# HPS_IOs.net
KiCad netlist of a schematic drawn in Altium Designer
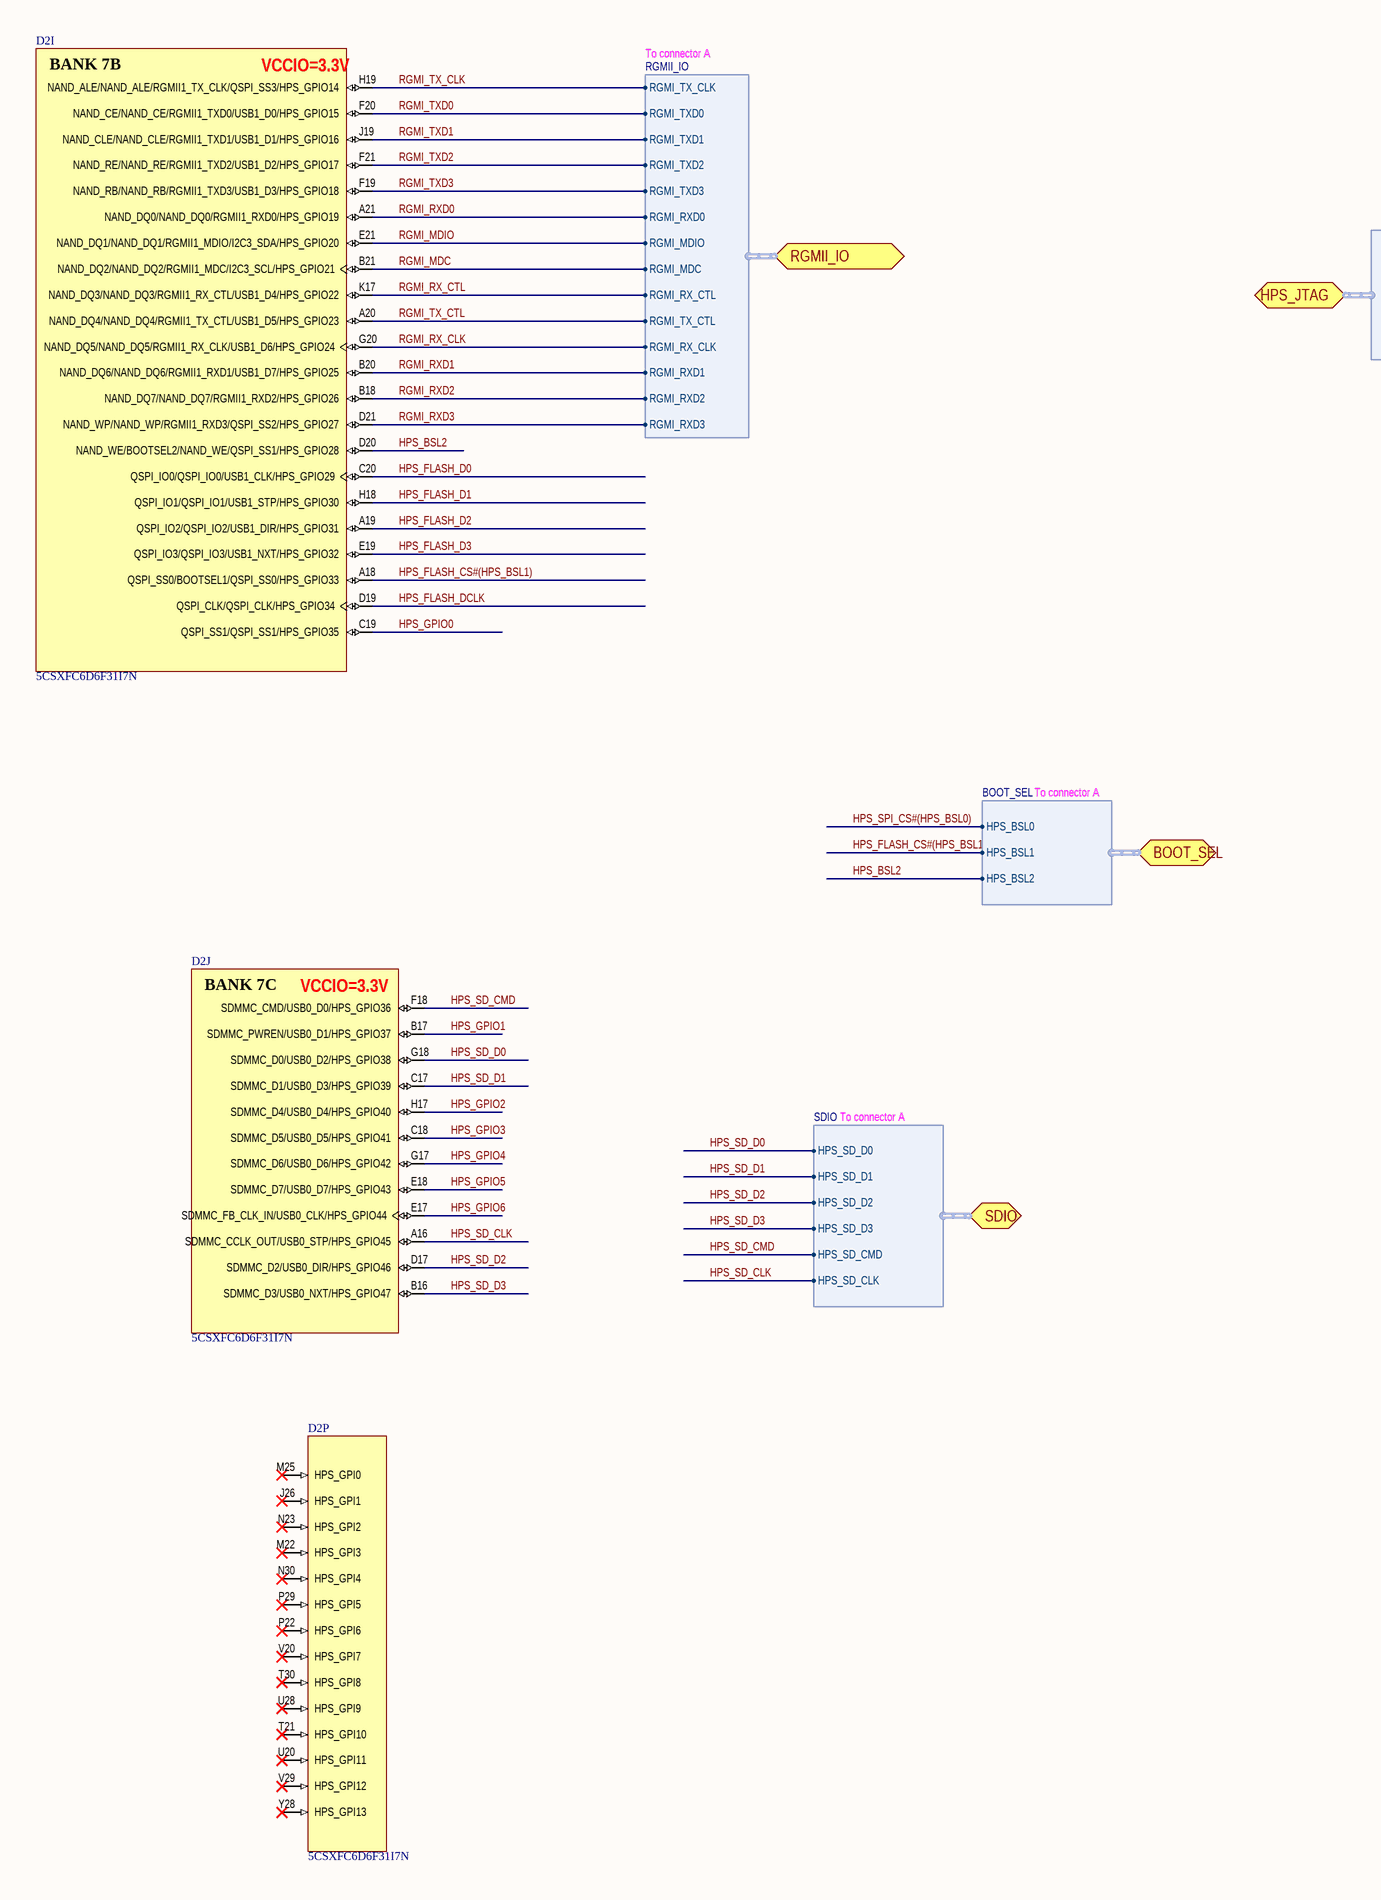
[diagram p0: HPS_IOs.SchDoc, left]
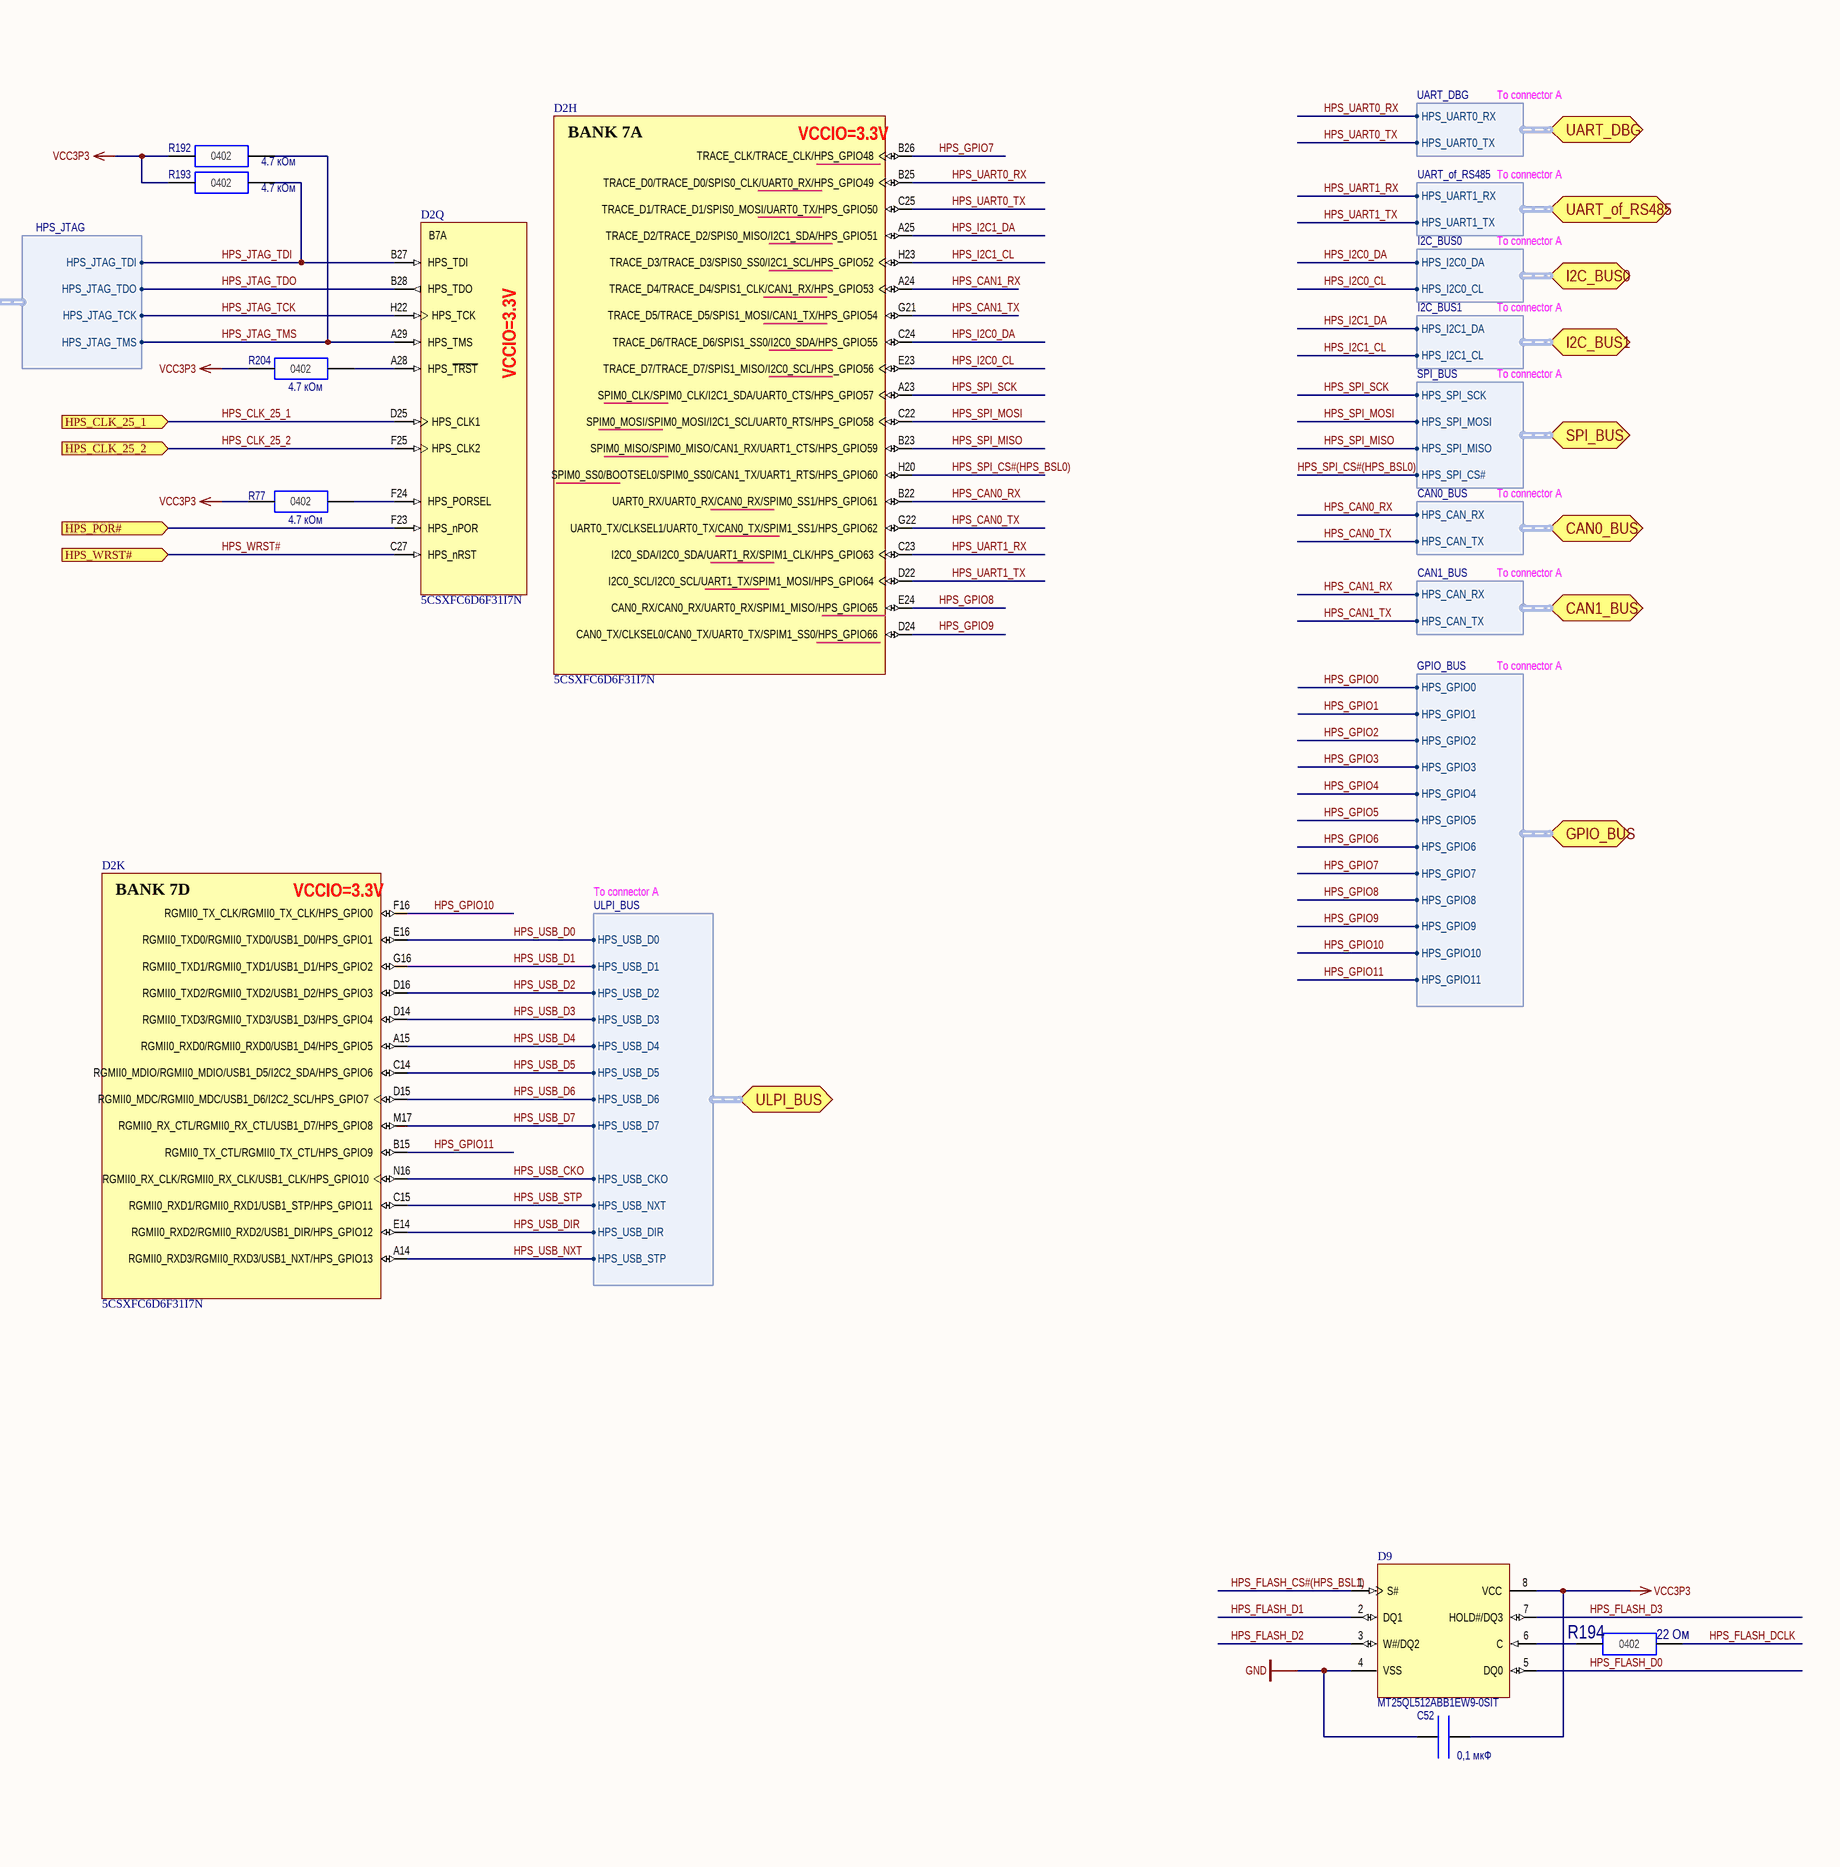
[diagram p1: HPS_IOs.SchDoc, right]

(export (version "E")
  (design (tool "Eeschema 10.0.6"))
  (components
    (comp (ref "C52")
      (value "0,1 мкФ")
      (footprint "CC0402(1005)")
      (description "Чип конденсатор керамический")
      (fields (field (name "Comment") "CC0402-X7R-0,1 мкФ-20%-10В"))
      (libsource (lib "Чип конденсаторы") (part "CC0402-X7R-#-20%-10В"))
    )
    (comp (ref "D2")
      (value "5CSXFC6D6F31I7N")
      (footprint "ALTR-FBGA896_A-200")
      (fields (field (name "MANUFACTURER") "Altera"))
      (libsource (lib "") (part "5CSXFC6D6F31I7N_1"))
    )
    (comp (ref "D9")
      (value "MT25QL512ABB1EW9-0SIT")
      (footprint "SON127P800X80_HS-9N")
      (fields (field (name "VOLTAGE") "2.7V-3.6V ") (field (name "MANUFACTURER") "Micron"))
      (libsource (lib "SD_IC") (part "MT25QL512ABB1EW9-0SIT"))
    )
    (comp (ref "R77")
      (value "4.7 кОм")
      (footprint "CR0402(1005)")
      (description "Чип резистор")
      (fields (field (name "TOLERANCE") "5%") (field (name "Comment") "CR0402-4.7 кОм-±5%"))
      (libsource (lib "Резисторы") (part "CR0402-#-±5%"))
    )
    (comp (ref "R192")
      (value "4.7 кОм")
      (footprint "CR0402(1005)")
      (description "Чип резистор")
      (fields (field (name "TOLERANCE") "5%") (field (name "Comment") "CR0402-4.7 кОм-±5%"))
      (libsource (lib "Резисторы") (part "CR0402-#-±5%"))
    )
    (comp (ref "R193")
      (value "4.7 кОм")
      (footprint "CR0402(1005)")
      (description "Чип резистор")
      (fields (field (name "TOLERANCE") "5%") (field (name "Comment") "CR0402-4.7 кОм-±5%"))
      (libsource (lib "Резисторы") (part "CR0402-#-±5%"))
    )
    (comp (ref "R194")
      (value "22 Ом")
      (footprint "CR0402(1005)")
      (description "Чип резистор")
      (fields (field (name "TOLERANCE") "5%") (field (name "Comment") "CR0402-22 Ом-±5%"))
      (libsource (lib "Чип резисторы") (part "CR0402-#-±5%"))
    )
    (comp (ref "R204")
      (value "4.7 кОм")
      (footprint "CR0402(1005)")
      (description "Чип резистор")
      (fields (field (name "TOLERANCE") "5%") (field (name "Comment") "CR0402-4.7 кОм-±5%"))
      (libsource (lib "Резисторы") (part "CR0402-#-±5%"))
    )
  )
  (nets
    (net (code "14") (name "/HPS_BSL2") (class "Default")
      (node (ref "D2") (pin "D20") (pinfunction "NAND_WE/BOOTSEL2/NAND_WE/QSPI_SS1/HPS_GPIO28_D20") (pintype "bidirectional"))
    )
    (net (code "15") (name "/HPS_CAN0_RX") (class "Default")
      (node (ref "D2") (pin "B22") (pinfunction "UART0_RX/UART0_RX/CAN0_RX/SPIM0_SS1/HPS_GPIO61_B22") (pintype "bidirectional"))
    )
    (net (code "16") (name "/HPS_CAN0_TX") (class "Default")
      (node (ref "D2") (pin "G22") (pinfunction "UART0_TX/CLKSEL1/UART0_TX/CAN0_TX/SPIM1_SS1/HPS_GPIO62_G22") (pintype "bidirectional"))
    )
    (net (code "17") (name "/HPS_CAN1_RX") (class "Default")
      (node (ref "D2") (pin "A24") (pinfunction "TRACE_D4/TRACE_D4/SPIS1_CLK/CAN1_RX/HPS_GPIO53_A24") (pintype "bidirectional"))
    )
    (net (code "18") (name "/HPS_CAN1_TX") (class "Default")
      (node (ref "D2") (pin "G21") (pinfunction "TRACE_D5/TRACE_D5/SPIS1_MOSI/CAN1_TX/HPS_GPIO54_G21") (pintype "bidirectional"))
    )
    (net (code "19") (name "/HPS_CLK_25_1") (class "Default")
      (node (ref "D2") (pin "D25") (pinfunction "HPS_CLK1_D25") (pintype "input"))
    )
    (net (code "20") (name "/HPS_CLK_25_2") (class "Default")
      (node (ref "D2") (pin "F25") (pinfunction "HPS_CLK2_F25") (pintype "input"))
    )
    (net (code "21") (name "/HPS_FLASH_CS#(HPS_BSL1)") (class "Default")
      (node (ref "D2") (pin "A18") (pinfunction "QSPI_SS0/BOOTSEL1/QSPI_SS0/HPS_GPIO33_A18") (pintype "bidirectional"))
      (node (ref "D9") (pin "1") (pinfunction "S#_1") (pintype "input"))
    )
    (net (code "22") (name "/HPS_FLASH_D0") (class "Default")
      (node (ref "D2") (pin "C20") (pinfunction "QSPI_IO0/QSPI_IO0/USB1_CLK/HPS_GPIO29_C20") (pintype "bidirectional"))
      (node (ref "D9") (pin "5") (pinfunction "DQ0_5") (pintype "bidirectional"))
    )
    (net (code "23") (name "/HPS_FLASH_D1") (class "Default")
      (node (ref "D2") (pin "H18") (pinfunction "QSPI_IO1/QSPI_IO1/USB1_STP/HPS_GPIO30_H18") (pintype "bidirectional"))
      (node (ref "D9") (pin "2") (pinfunction "DQ1_2") (pintype "bidirectional"))
    )
    (net (code "24") (name "/HPS_FLASH_D2") (class "Default")
      (node (ref "D2") (pin "A19") (pinfunction "QSPI_IO2/QSPI_IO2/USB1_DIR/HPS_GPIO31_A19") (pintype "bidirectional"))
      (node (ref "D9") (pin "3") (pinfunction "W#/DQ2_3") (pintype "bidirectional"))
    )
    (net (code "25") (name "/HPS_FLASH_D3") (class "Default")
      (node (ref "D2") (pin "E19") (pinfunction "QSPI_IO3/QSPI_IO3/USB1_NXT/HPS_GPIO32_E19") (pintype "bidirectional"))
      (node (ref "D9") (pin "7") (pinfunction "HOLD#/DQ3_7") (pintype "bidirectional"))
    )
    (net (code "26") (name "/HPS_FLASH_DCLK") (class "Default")
      (node (ref "D2") (pin "D19") (pinfunction "QSPI_CLK/QSPI_CLK/HPS_GPIO34_D19") (pintype "bidirectional"))
      (node (ref "R194") (pin "2") (pinfunction "-_2") (pintype "passive"))
    )
    (net (code "27") (name "/HPS_GPIO0") (class "Default")
      (node (ref "D2") (pin "C19") (pinfunction "QSPI_SS1/QSPI_SS1/HPS_GPIO35_C19") (pintype "bidirectional"))
    )
    (net (code "28") (name "/HPS_GPIO1") (class "Default")
      (node (ref "D2") (pin "B17") (pinfunction "SDMMC_PWREN/USB0_D1/HPS_GPIO37_B17") (pintype "bidirectional"))
    )
    (net (code "29") (name "/HPS_GPIO2") (class "Default")
      (node (ref "D2") (pin "H17") (pinfunction "SDMMC_D4/USB0_D4/HPS_GPIO40_H17") (pintype "bidirectional"))
    )
    (net (code "30") (name "/HPS_GPIO3") (class "Default")
      (node (ref "D2") (pin "C18") (pinfunction "SDMMC_D5/USB0_D5/HPS_GPIO41_C18") (pintype "bidirectional"))
    )
    (net (code "31") (name "/HPS_GPIO4") (class "Default")
      (node (ref "D2") (pin "G17") (pinfunction "SDMMC_D6/USB0_D6/HPS_GPIO42_G17") (pintype "bidirectional"))
    )
    (net (code "32") (name "/HPS_GPIO5") (class "Default")
      (node (ref "D2") (pin "E18") (pinfunction "SDMMC_D7/USB0_D7/HPS_GPIO43_E18") (pintype "bidirectional"))
    )
    (net (code "33") (name "/HPS_GPIO6") (class "Default")
      (node (ref "D2") (pin "E17") (pinfunction "SDMMC_FB_CLK_IN/USB0_CLK/HPS_GPIO44_E17") (pintype "bidirectional"))
    )
    (net (code "34") (name "/HPS_GPIO7") (class "Default")
      (node (ref "D2") (pin "B26") (pinfunction "TRACE_CLK/TRACE_CLK/HPS_GPIO48_B26") (pintype "bidirectional"))
    )
    (net (code "35") (name "/HPS_GPIO8") (class "Default")
      (node (ref "D2") (pin "E24") (pinfunction "CAN0_RX/CAN0_RX/UART0_RX/SPIM1_MISO/HPS_GPIO65_E24") (pintype "bidirectional"))
    )
    (net (code "36") (name "/HPS_GPIO9") (class "Default")
      (node (ref "D2") (pin "D24") (pinfunction "CAN0_TX/CLKSEL0/CAN0_TX/UART0_TX/SPIM1_SS0/HPS_GPIO66_D24") (pintype "bidirectional"))
    )
    (net (code "37") (name "/HPS_GPIO10") (class "Default")
      (node (ref "D2") (pin "F16") (pinfunction "RGMII0_TX_CLK/RGMII0_TX_CLK/HPS_GPIO0_F16") (pintype "bidirectional"))
    )
    (net (code "38") (name "/HPS_GPIO11") (class "Default")
      (node (ref "D2") (pin "B15") (pinfunction "RGMII0_TX_CTL/RGMII0_TX_CTL/HPS_GPIO9_B15") (pintype "bidirectional"))
    )
    (net (code "39") (name "/HPS_I2C0_CL") (class "Default")
      (node (ref "D2") (pin "E23") (pinfunction "TRACE_D7/TRACE_D7/SPIS1_MISO/I2C0_SCL/HPS_GPIO56_E23") (pintype "bidirectional"))
    )
    (net (code "40") (name "/HPS_I2C0_DA") (class "Default")
      (node (ref "D2") (pin "C24") (pinfunction "TRACE_D6/TRACE_D6/SPIS1_SS0/I2C0_SDA/HPS_GPIO55_C24") (pintype "bidirectional"))
    )
    (net (code "41") (name "/HPS_I2C1_CL") (class "Default")
      (node (ref "D2") (pin "H23") (pinfunction "TRACE_D3/TRACE_D3/SPIS0_SS0/I2C1_SCL/HPS_GPIO52_H23") (pintype "bidirectional"))
    )
    (net (code "42") (name "/HPS_I2C1_DA") (class "Default")
      (node (ref "D2") (pin "A25") (pinfunction "TRACE_D2/TRACE_D2/SPIS0_MISO/I2C1_SDA/HPS_GPIO51_A25") (pintype "bidirectional"))
    )
    (net (code "43") (name "/HPS_JTAG_TCK") (class "Default")
      (node (ref "D2") (pin "H22") (pinfunction "HPS_TCK_H22") (pintype "input"))
    )
    (net (code "44") (name "/HPS_JTAG_TDI") (class "Default")
      (node (ref "D2") (pin "B27") (pinfunction "HPS_TDI_B27") (pintype "input"))
      (node (ref "R193") (pin "2") (pinfunction "-_2") (pintype "passive"))
    )
    (net (code "45") (name "/HPS_JTAG_TDO") (class "Default")
      (node (ref "D2") (pin "B28") (pinfunction "HPS_TDO_B28") (pintype "output"))
    )
    (net (code "46") (name "/HPS_JTAG_TMS") (class "Default")
      (node (ref "D2") (pin "A29") (pinfunction "HPS_TMS_A29") (pintype "input"))
      (node (ref "R192") (pin "2") (pinfunction "-_2") (pintype "passive"))
    )
    (net (code "47") (name "/HPS_POR#") (class "Default")
      (node (ref "D2") (pin "F23") (pinfunction "HPS_nPOR_F23") (pintype "input"))
    )
    (net (code "48") (name "/HPS_SD_CLK") (class "Default")
      (node (ref "D2") (pin "A16") (pinfunction "SDMMC_CCLK_OUT/USB0_STP/HPS_GPIO45_A16") (pintype "bidirectional"))
    )
    (net (code "49") (name "/HPS_SD_CMD") (class "Default")
      (node (ref "D2") (pin "F18") (pinfunction "SDMMC_CMD/USB0_D0/HPS_GPIO36_F18") (pintype "bidirectional"))
    )
    (net (code "50") (name "/HPS_SD_D0") (class "Default")
      (node (ref "D2") (pin "G18") (pinfunction "SDMMC_D0/USB0_D2/HPS_GPIO38_G18") (pintype "bidirectional"))
    )
    (net (code "51") (name "/HPS_SD_D1") (class "Default")
      (node (ref "D2") (pin "C17") (pinfunction "SDMMC_D1/USB0_D3/HPS_GPIO39_C17") (pintype "bidirectional"))
    )
    (net (code "52") (name "/HPS_SD_D2") (class "Default")
      (node (ref "D2") (pin "D17") (pinfunction "SDMMC_D2/USB0_DIR/HPS_GPIO46_D17") (pintype "bidirectional"))
    )
    (net (code "53") (name "/HPS_SD_D3") (class "Default")
      (node (ref "D2") (pin "B16") (pinfunction "SDMMC_D3/USB0_NXT/HPS_GPIO47_B16") (pintype "bidirectional"))
    )
    (net (code "54") (name "/HPS_SPI_CS#(HPS_BSL0)") (class "Default")
      (node (ref "D2") (pin "H20") (pinfunction "SPIM0_SS0/BOOTSEL0/SPIM0_SS0/CAN1_TX/UART1_RTS/HPS_GPIO60_H20") (pintype "bidirectional"))
    )
    (net (code "55") (name "/HPS_SPI_MISO") (class "Default")
      (node (ref "D2") (pin "B23") (pinfunction "SPIM0_MISO/SPIM0_MISO/CAN1_RX/UART1_CTS/HPS_GPIO59_B23") (pintype "bidirectional"))
    )
    (net (code "56") (name "/HPS_SPI_MOSI") (class "Default")
      (node (ref "D2") (pin "C22") (pinfunction "SPIM0_MOSI/SPIM0_MOSI/I2C1_SCL/UART0_RTS/HPS_GPIO58_C22") (pintype "bidirectional"))
    )
    (net (code "57") (name "/HPS_SPI_SCK") (class "Default")
      (node (ref "D2") (pin "A23") (pinfunction "SPIM0_CLK/SPIM0_CLK/I2C1_SDA/UART0_CTS/HPS_GPIO57_A23") (pintype "bidirectional"))
    )
    (net (code "58") (name "/HPS_UART0_RX") (class "Default")
      (node (ref "D2") (pin "B25") (pinfunction "TRACE_D0/TRACE_D0/SPIS0_CLK/UART0_RX/HPS_GPIO49_B25") (pintype "bidirectional"))
    )
    (net (code "59") (name "/HPS_UART0_TX") (class "Default")
      (node (ref "D2") (pin "C25") (pinfunction "TRACE_D1/TRACE_D1/SPIS0_MOSI/UART0_TX/HPS_GPIO50_C25") (pintype "bidirectional"))
    )
    (net (code "60") (name "/HPS_UART1_RX") (class "Default")
      (node (ref "D2") (pin "C23") (pinfunction "I2C0_SDA/I2C0_SDA/UART1_RX/SPIM1_CLK/HPS_GPIO63_C23") (pintype "bidirectional"))
    )
    (net (code "61") (name "/HPS_UART1_TX") (class "Default")
      (node (ref "D2") (pin "D22") (pinfunction "I2C0_SCL/I2C0_SCL/UART1_TX/SPIM1_MOSI/HPS_GPIO64_D22") (pintype "bidirectional"))
    )
    (net (code "62") (name "/HPS_USB_CKO") (class "Default")
      (node (ref "D2") (pin "N16") (pinfunction "RGMII0_RX_CLK/RGMII0_RX_CLK/USB1_CLK/HPS_GPIO10_N16") (pintype "bidirectional"))
    )
    (net (code "63") (name "/HPS_USB_D0") (class "Default")
      (node (ref "D2") (pin "E16") (pinfunction "RGMII0_TXD0/RGMII0_TXD0/USB1_D0/HPS_GPIO1_E16") (pintype "bidirectional"))
    )
    (net (code "64") (name "/HPS_USB_D1") (class "Default")
      (node (ref "D2") (pin "G16") (pinfunction "RGMII0_TXD1/RGMII0_TXD1/USB1_D1/HPS_GPIO2_G16") (pintype "bidirectional"))
    )
    (net (code "65") (name "/HPS_USB_D2") (class "Default")
      (node (ref "D2") (pin "D16") (pinfunction "RGMII0_TXD2/RGMII0_TXD2/USB1_D2/HPS_GPIO3_D16") (pintype "bidirectional"))
    )
    (net (code "66") (name "/HPS_USB_D3") (class "Default")
      (node (ref "D2") (pin "D14") (pinfunction "RGMII0_TXD3/RGMII0_TXD3/USB1_D3/HPS_GPIO4_D14") (pintype "bidirectional"))
    )
    (net (code "67") (name "/HPS_USB_D4") (class "Default")
      (node (ref "D2") (pin "A15") (pinfunction "RGMII0_RXD0/RGMII0_RXD0/USB1_D4/HPS_GPIO5_A15") (pintype "bidirectional"))
    )
    (net (code "68") (name "/HPS_USB_D5") (class "Default")
      (node (ref "D2") (pin "C14") (pinfunction "RGMII0_MDIO/RGMII0_MDIO/USB1_D5/I2C2_SDA/HPS_GPIO6_C14") (pintype "bidirectional"))
    )
    (net (code "69") (name "/HPS_USB_D6") (class "Default")
      (node (ref "D2") (pin "D15") (pinfunction "RGMII0_MDC/RGMII0_MDC/USB1_D6/I2C2_SCL/HPS_GPIO7_D15") (pintype "bidirectional"))
    )
    (net (code "70") (name "/HPS_USB_D7") (class "Default")
      (node (ref "D2") (pin "M17") (pinfunction "RGMII0_RX_CTL/RGMII0_RX_CTL/USB1_D7/HPS_GPIO8_M17") (pintype "bidirectional"))
    )
    (net (code "71") (name "/HPS_USB_DIR") (class "Default")
      (node (ref "D2") (pin "E14") (pinfunction "RGMII0_RXD2/RGMII0_RXD2/USB1_DIR/HPS_GPIO12_E14") (pintype "bidirectional"))
    )
    (net (code "72") (name "/HPS_USB_NXT") (class "Default")
      (node (ref "D2") (pin "A14") (pinfunction "RGMII0_RXD3/RGMII0_RXD3/USB1_NXT/HPS_GPIO13_A14") (pintype "bidirectional"))
    )
    (net (code "73") (name "/HPS_USB_STP") (class "Default")
      (node (ref "D2") (pin "C15") (pinfunction "RGMII0_RXD1/RGMII0_RXD1/USB1_STP/HPS_GPIO11_C15") (pintype "bidirectional"))
    )
    (net (code "74") (name "/HPS_WRST#") (class "Default")
      (node (ref "D2") (pin "C27") (pinfunction "HPS_nRST_C27") (pintype "input"))
    )
    (net (code "75") (name "/RGMI_MDC") (class "Default")
      (node (ref "D2") (pin "B21") (pinfunction "NAND_DQ2/NAND_DQ2/RGMII1_MDC/I2C3_SCL/HPS_GPIO21_B21") (pintype "bidirectional"))
    )
    (net (code "76") (name "/RGMI_MDIO") (class "Default")
      (node (ref "D2") (pin "E21") (pinfunction "NAND_DQ1/NAND_DQ1/RGMII1_MDIO/I2C3_SDA/HPS_GPIO20_E21") (pintype "bidirectional"))
    )
    (net (code "77") (name "/RGMI_RXD0") (class "Default")
      (node (ref "D2") (pin "A21") (pinfunction "NAND_DQ0/NAND_DQ0/RGMII1_RXD0/HPS_GPIO19_A21") (pintype "bidirectional"))
    )
    (net (code "78") (name "/RGMI_RXD1") (class "Default")
      (node (ref "D2") (pin "B20") (pinfunction "NAND_DQ6/NAND_DQ6/RGMII1_RXD1/USB1_D7/HPS_GPIO25_B20") (pintype "bidirectional"))
    )
    (net (code "79") (name "/RGMI_RXD2") (class "Default")
      (node (ref "D2") (pin "B18") (pinfunction "NAND_DQ7/NAND_DQ7/RGMII1_RXD2/HPS_GPIO26_B18") (pintype "bidirectional"))
    )
    (net (code "80") (name "/RGMI_RXD3") (class "Default")
      (node (ref "D2") (pin "D21") (pinfunction "NAND_WP/NAND_WP/RGMII1_RXD3/QSPI_SS2/HPS_GPIO27_D21") (pintype "bidirectional"))
    )
    (net (code "81") (name "/RGMI_RX_CLK") (class "Default")
      (node (ref "D2") (pin "G20") (pinfunction "NAND_DQ5/NAND_DQ5/RGMII1_RX_CLK/USB1_D6/HPS_GPIO24_G20") (pintype "bidirectional"))
    )
    (net (code "82") (name "/RGMI_RX_CTL") (class "Default")
      (node (ref "D2") (pin "K17") (pinfunction "NAND_DQ3/NAND_DQ3/RGMII1_RX_CTL/USB1_D4/HPS_GPIO22_K17") (pintype "bidirectional"))
    )
    (net (code "83") (name "/RGMI_TXD0") (class "Default")
      (node (ref "D2") (pin "F20") (pinfunction "NAND_CE/NAND_CE/RGMII1_TXD0/USB1_D0/HPS_GPIO15_F20") (pintype "bidirectional"))
    )
    (net (code "84") (name "/RGMI_TXD1") (class "Default")
      (node (ref "D2") (pin "J19") (pinfunction "NAND_CLE/NAND_CLE/RGMII1_TXD1/USB1_D1/HPS_GPIO16_J19") (pintype "bidirectional"))
    )
    (net (code "85") (name "/RGMI_TXD2") (class "Default")
      (node (ref "D2") (pin "F21") (pinfunction "NAND_RE/NAND_RE/RGMII1_TXD2/USB1_D2/HPS_GPIO17_F21") (pintype "bidirectional"))
    )
    (net (code "86") (name "/RGMI_TXD3") (class "Default")
      (node (ref "D2") (pin "F19") (pinfunction "NAND_RB/NAND_RB/RGMII1_TXD3/USB1_D3/HPS_GPIO18_F19") (pintype "bidirectional"))
    )
    (net (code "87") (name "/RGMI_TX_CLK") (class "Default")
      (node (ref "D2") (pin "H19") (pinfunction "NAND_ALE/NAND_ALE/RGMII1_TX_CLK/QSPI_SS3/HPS_GPIO14_H19") (pintype "bidirectional"))
    )
    (net (code "88") (name "/RGMI_TX_CTL") (class "Default")
      (node (ref "D2") (pin "A20") (pinfunction "NAND_DQ4/NAND_DQ4/RGMII1_TX_CTL/USB1_D5/HPS_GPIO23_A20") (pintype "bidirectional"))
    )
    (net (code "102") (name "GND") (class "Default")
      (node (ref "C52") (pin "1") (pinfunction "+_1") (pintype "passive"))
      (node (ref "D9") (pin "4") (pinfunction "VSS_4") (pintype "power_in"))
    )
    (net (code "103") (name "Net-(D2Q-HPS_PORSEL)") (class "Default")
      (node (ref "D2") (pin "F24") (pinfunction "HPS_PORSEL_F24") (pintype "input"))
      (node (ref "R77") (pin "2") (pinfunction "-_2") (pintype "passive"))
    )
    (net (code "104") (name "Net-(D2Q-HPS_~{TRST})") (class "Default")
      (node (ref "D2") (pin "A28") (pinfunction "HPS_~{TRST}_A28") (pintype "input"))
      (node (ref "R204") (pin "2") (pinfunction "-_2") (pintype "passive"))
    )
    (net (code "105") (name "Net-(D9-C)") (class "Default")
      (node (ref "D9") (pin "6") (pinfunction "C_6") (pintype "input"))
      (node (ref "R194") (pin "1") (pinfunction "+_1") (pintype "passive"))
    )
    (net (code "106") (name "VCC3P3") (class "Default")
      (node (ref "C52") (pin "2") (pinfunction "-_2") (pintype "passive"))
      (node (ref "D9") (pin "8") (pinfunction "VCC_8") (pintype "power_in"))
      (node (ref "R192") (pin "1") (pinfunction "+_1") (pintype "passive"))
      (node (ref "R193") (pin "1") (pinfunction "+_1") (pintype "passive"))
      (node (ref "R204") (pin "1") (pinfunction "+_1") (pintype "passive"))
      (node (ref "R77") (pin "1") (pinfunction "+_1") (pintype "passive"))
    )
    (net (code "107") (name "unconnected-(D2P-HPS_GPI0-PadM25)") (class "Default")
      (node (ref "D2") (pin "M25") (pinfunction "HPS_GPI0_M25") (pintype "input+no_connect"))
    )
    (net (code "108") (name "unconnected-(D2P-HPS_GPI1-PadJ26)") (class "Default")
      (node (ref "D2") (pin "J26") (pinfunction "HPS_GPI1_J26") (pintype "input+no_connect"))
    )
    (net (code "109") (name "unconnected-(D2P-HPS_GPI2-PadN23)") (class "Default")
      (node (ref "D2") (pin "N23") (pinfunction "HPS_GPI2_N23") (pintype "input+no_connect"))
    )
    (net (code "110") (name "unconnected-(D2P-HPS_GPI3-PadM22)") (class "Default")
      (node (ref "D2") (pin "M22") (pinfunction "HPS_GPI3_M22") (pintype "input+no_connect"))
    )
    (net (code "111") (name "unconnected-(D2P-HPS_GPI4-PadN30)") (class "Default")
      (node (ref "D2") (pin "N30") (pinfunction "HPS_GPI4_N30") (pintype "input+no_connect"))
    )
    (net (code "112") (name "unconnected-(D2P-HPS_GPI5-PadP29)") (class "Default")
      (node (ref "D2") (pin "P29") (pinfunction "HPS_GPI5_P29") (pintype "input+no_connect"))
    )
    (net (code "113") (name "unconnected-(D2P-HPS_GPI6-PadP22)") (class "Default")
      (node (ref "D2") (pin "P22") (pinfunction "HPS_GPI6_P22") (pintype "input+no_connect"))
    )
    (net (code "114") (name "unconnected-(D2P-HPS_GPI7-PadV20)") (class "Default")
      (node (ref "D2") (pin "V20") (pinfunction "HPS_GPI7_V20") (pintype "input+no_connect"))
    )
    (net (code "115") (name "unconnected-(D2P-HPS_GPI8-PadT30)") (class "Default")
      (node (ref "D2") (pin "T30") (pinfunction "HPS_GPI8_T30") (pintype "input+no_connect"))
    )
    (net (code "116") (name "unconnected-(D2P-HPS_GPI9-PadU28)") (class "Default")
      (node (ref "D2") (pin "U28") (pinfunction "HPS_GPI9_U28") (pintype "input+no_connect"))
    )
    (net (code "117") (name "unconnected-(D2P-HPS_GPI10-PadT21)") (class "Default")
      (node (ref "D2") (pin "T21") (pinfunction "HPS_GPI10_T21") (pintype "input+no_connect"))
    )
    (net (code "118") (name "unconnected-(D2P-HPS_GPI11-PadU20)") (class "Default")
      (node (ref "D2") (pin "U20") (pinfunction "HPS_GPI11_U20") (pintype "input+no_connect"))
    )
    (net (code "119") (name "unconnected-(D2P-HPS_GPI12-PadV29)") (class "Default")
      (node (ref "D2") (pin "V29") (pinfunction "HPS_GPI12_V29") (pintype "input+no_connect"))
    )
    (net (code "120") (name "unconnected-(D2P-HPS_GPI13-PadY28)") (class "Default")
      (node (ref "D2") (pin "Y28") (pinfunction "HPS_GPI13_Y28") (pintype "input+no_connect"))
    )
  )
)
